# ICE40.net
KiCad netlist of a schematic drawn in Altium Designer
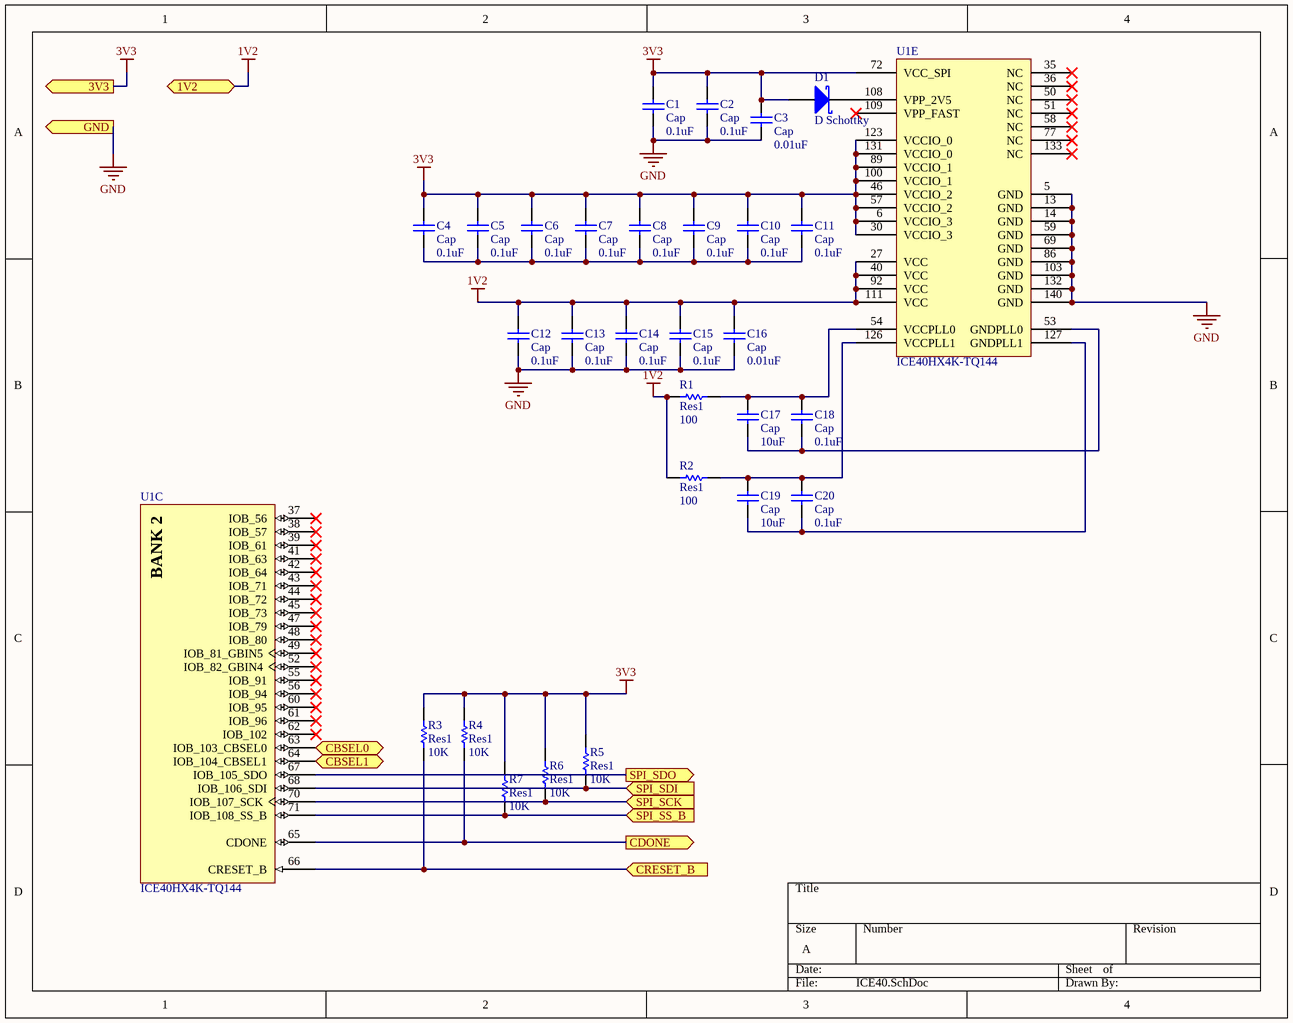
[diagram p0: ICE40.SchDoc]

(export (version "E")
  (design (tool "Eeschema 10.0.6"))
  (components
    (comp (ref "C1")
      (value "Cap")
      (footprint "RAD-0.3")
      (description "Capacitor")
      (fields (field (name "ALTIUM_VALUE") "0.1uF") (field (name "PUBLISHER") "Altium Limited"))
      (libsource (lib "Miscellaneous Devices") (part "Cap"))
    )
    (comp (ref "C2")
      (value "Cap")
      (footprint "RAD-0.3")
      (description "Capacitor")
      (fields (field (name "ALTIUM_VALUE") "0.1uF") (field (name "PUBLISHER") "Altium Limited"))
      (libsource (lib "Miscellaneous Devices") (part "Cap"))
    )
    (comp (ref "C3")
      (value "Cap")
      (footprint "RAD-0.3")
      (description "Capacitor")
      (fields (field (name "ALTIUM_VALUE") "0.01uF") (field (name "PUBLISHER") "Altium Limited"))
      (libsource (lib "Miscellaneous Devices") (part "Cap"))
    )
    (comp (ref "C4")
      (value "Cap")
      (footprint "RAD-0.3")
      (description "Capacitor")
      (fields (field (name "ALTIUM_VALUE") "0.1uF") (field (name "PUBLISHER") "Altium Limited"))
      (libsource (lib "Miscellaneous Devices") (part "Cap"))
    )
    (comp (ref "C5")
      (value "Cap")
      (footprint "RAD-0.3")
      (description "Capacitor")
      (fields (field (name "ALTIUM_VALUE") "0.1uF") (field (name "PUBLISHER") "Altium Limited"))
      (libsource (lib "Miscellaneous Devices") (part "Cap"))
    )
    (comp (ref "C6")
      (value "Cap")
      (footprint "RAD-0.3")
      (description "Capacitor")
      (fields (field (name "ALTIUM_VALUE") "0.1uF") (field (name "PUBLISHER") "Altium Limited"))
      (libsource (lib "Miscellaneous Devices") (part "Cap"))
    )
    (comp (ref "C7")
      (value "Cap")
      (footprint "RAD-0.3")
      (description "Capacitor")
      (fields (field (name "ALTIUM_VALUE") "0.1uF") (field (name "PUBLISHER") "Altium Limited"))
      (libsource (lib "Miscellaneous Devices") (part "Cap"))
    )
    (comp (ref "C8")
      (value "Cap")
      (footprint "RAD-0.3")
      (description "Capacitor")
      (fields (field (name "ALTIUM_VALUE") "0.1uF") (field (name "PUBLISHER") "Altium Limited"))
      (libsource (lib "Miscellaneous Devices") (part "Cap"))
    )
    (comp (ref "C9")
      (value "Cap")
      (footprint "RAD-0.3")
      (description "Capacitor")
      (fields (field (name "ALTIUM_VALUE") "0.1uF") (field (name "PUBLISHER") "Altium Limited"))
      (libsource (lib "Miscellaneous Devices") (part "Cap"))
    )
    (comp (ref "C10")
      (value "Cap")
      (footprint "RAD-0.3")
      (description "Capacitor")
      (fields (field (name "ALTIUM_VALUE") "0.1uF") (field (name "PUBLISHER") "Altium Limited"))
      (libsource (lib "Miscellaneous Devices") (part "Cap"))
    )
    (comp (ref "C11")
      (value "Cap")
      (footprint "RAD-0.3")
      (description "Capacitor")
      (fields (field (name "ALTIUM_VALUE") "0.1uF") (field (name "PUBLISHER") "Altium Limited"))
      (libsource (lib "Miscellaneous Devices") (part "Cap"))
    )
    (comp (ref "C12")
      (value "Cap")
      (footprint "RAD-0.3")
      (description "Capacitor")
      (fields (field (name "ALTIUM_VALUE") "0.1uF") (field (name "PUBLISHER") "Altium Limited"))
      (libsource (lib "Miscellaneous Devices") (part "Cap"))
    )
    (comp (ref "C13")
      (value "Cap")
      (footprint "RAD-0.3")
      (description "Capacitor")
      (fields (field (name "ALTIUM_VALUE") "0.1uF") (field (name "PUBLISHER") "Altium Limited"))
      (libsource (lib "Miscellaneous Devices") (part "Cap"))
    )
    (comp (ref "C14")
      (value "Cap")
      (footprint "RAD-0.3")
      (description "Capacitor")
      (fields (field (name "ALTIUM_VALUE") "0.1uF") (field (name "PUBLISHER") "Altium Limited"))
      (libsource (lib "Miscellaneous Devices") (part "Cap"))
    )
    (comp (ref "C15")
      (value "Cap")
      (footprint "RAD-0.3")
      (description "Capacitor")
      (fields (field (name "ALTIUM_VALUE") "0.1uF") (field (name "PUBLISHER") "Altium Limited"))
      (libsource (lib "Miscellaneous Devices") (part "Cap"))
    )
    (comp (ref "C16")
      (value "Cap")
      (footprint "RAD-0.3")
      (description "Capacitor")
      (fields (field (name "ALTIUM_VALUE") "0.01uF") (field (name "PUBLISHER") "Altium Limited"))
      (libsource (lib "Miscellaneous Devices") (part "Cap"))
    )
    (comp (ref "C17")
      (value "Cap")
      (footprint "RAD-0.3")
      (description "Capacitor")
      (fields (field (name "ALTIUM_VALUE") "10uF") (field (name "PUBLISHER") "Altium Limited"))
      (libsource (lib "Miscellaneous Devices") (part "Cap"))
    )
    (comp (ref "C18")
      (value "Cap")
      (footprint "RAD-0.3")
      (description "Capacitor")
      (fields (field (name "ALTIUM_VALUE") "0.1uF") (field (name "PUBLISHER") "Altium Limited"))
      (libsource (lib "Miscellaneous Devices") (part "Cap"))
    )
    (comp (ref "C19")
      (value "Cap")
      (footprint "RAD-0.3")
      (description "Capacitor")
      (fields (field (name "ALTIUM_VALUE") "10uF") (field (name "PUBLISHER") "Altium Limited"))
      (libsource (lib "Miscellaneous Devices") (part "Cap"))
    )
    (comp (ref "C20")
      (value "Cap")
      (footprint "RAD-0.3")
      (description "Capacitor")
      (fields (field (name "ALTIUM_VALUE") "0.1uF") (field (name "PUBLISHER") "Altium Limited"))
      (libsource (lib "Miscellaneous Devices") (part "Cap"))
    )
    (comp (ref "D1")
      (value "D Schottky")
      (footprint "SMB")
      (description "Schottky Diode")
      (fields (field (name "PUBLISHER") "Altium Limited"))
      (libsource (lib "Miscellaneous Devices") (part "D Schottky"))
    )
    (comp (ref "R1")
      (value "Res1")
      (footprint "AXIAL-0.3")
      (description "Resistor")
      (fields (field (name "ALTIUM_VALUE") "100") (field (name "PUBLISHER") "Altium Limited"))
      (libsource (lib "Miscellaneous Devices") (part "Res1"))
    )
    (comp (ref "R2")
      (value "Res1")
      (footprint "AXIAL-0.3")
      (description "Resistor")
      (fields (field (name "ALTIUM_VALUE") "100") (field (name "PUBLISHER") "Altium Limited"))
      (libsource (lib "Miscellaneous Devices") (part "Res1"))
    )
    (comp (ref "R3")
      (value "Res1")
      (footprint "AXIAL-0.3")
      (description "Resistor")
      (fields (field (name "ALTIUM_VALUE") "10K") (field (name "PUBLISHER") "Altium Limited"))
      (libsource (lib "Miscellaneous Devices") (part "Res1"))
    )
    (comp (ref "R4")
      (value "Res1")
      (footprint "AXIAL-0.3")
      (description "Resistor")
      (fields (field (name "ALTIUM_VALUE") "10K") (field (name "PUBLISHER") "Altium Limited"))
      (libsource (lib "Miscellaneous Devices") (part "Res1"))
    )
    (comp (ref "R5")
      (value "Res1")
      (footprint "AXIAL-0.3")
      (description "Resistor")
      (fields (field (name "ALTIUM_VALUE") "10K") (field (name "PUBLISHER") "Altium Limited"))
      (libsource (lib "Miscellaneous Devices") (part "Res1"))
    )
    (comp (ref "R6")
      (value "Res1")
      (footprint "AXIAL-0.3")
      (description "Resistor")
      (fields (field (name "ALTIUM_VALUE") "10K") (field (name "PUBLISHER") "Altium Limited"))
      (libsource (lib "Miscellaneous Devices") (part "Res1"))
    )
    (comp (ref "R7")
      (value "Res1")
      (footprint "AXIAL-0.3")
      (description "Resistor")
      (fields (field (name "ALTIUM_VALUE") "10K") (field (name "PUBLISHER") "Altium Limited"))
      (libsource (lib "Miscellaneous Devices") (part "Res1"))
    )
    (comp (ref "U1")
      (value "ICE40HX4K-TQ144")
      (footprint "LATC-TQFP-144_M")
      (fields (field (name "MANUFACTURER") "Lattice Semiconductor"))
      (libsource (lib "Lattice iCE40") (part "ICE40HX4K-TQ144"))
    )
  )
  (nets
    (net (code "1") (name "/CBSEL0") (class "Default")
      (node (ref "U1") (pin "63") (pinfunction "IOB_103_CBSEL0_63") (pintype "bidirectional"))
    )
    (net (code "2") (name "/CBSEL1") (class "Default")
      (node (ref "U1") (pin "64") (pinfunction "IOB_104_CBSEL1_64") (pintype "bidirectional"))
    )
    (net (code "3") (name "/CDONE") (class "Default")
      (node (ref "R4") (pin "1") (pinfunction "1_1") (pintype "passive"))
      (node (ref "U1") (pin "65") (pinfunction "CDONE_65") (pintype "bidirectional"))
    )
    (net (code "4") (name "/CRESET_B") (class "Default")
      (node (ref "R3") (pin "1") (pinfunction "1_1") (pintype "passive"))
      (node (ref "U1") (pin "66") (pinfunction "CRESET_B_66") (pintype "input"))
    )
    (net (code "5") (name "/SPI_SCK") (class "Default")
      (node (ref "R6") (pin "1") (pinfunction "1_1") (pintype "passive"))
      (node (ref "U1") (pin "70") (pinfunction "IOB_107_SCK_70") (pintype "bidirectional"))
    )
    (net (code "6") (name "/SPI_SDI") (class "Default")
      (node (ref "R5") (pin "1") (pinfunction "1_1") (pintype "passive"))
      (node (ref "U1") (pin "68") (pinfunction "IOB_106_SDI_68") (pintype "bidirectional"))
    )
    (net (code "7") (name "/SPI_SDO") (class "Default")
      (node (ref "U1") (pin "67") (pinfunction "IOB_105_SDO_67") (pintype "bidirectional"))
    )
    (net (code "8") (name "/SPI_SS_B") (class "Default")
      (node (ref "R7") (pin "1") (pinfunction "1_1") (pintype "passive"))
      (node (ref "U1") (pin "71") (pinfunction "IOB_108_SS_B_71") (pintype "bidirectional"))
    )
    (net (code "9") (name "1V2") (class "Default")
      (node (ref "C12") (pin "1") (pinfunction "1_1") (pintype "passive"))
      (node (ref "C13") (pin "1") (pinfunction "1_1") (pintype "passive"))
      (node (ref "C14") (pin "1") (pinfunction "1_1") (pintype "passive"))
      (node (ref "C15") (pin "1") (pinfunction "1_1") (pintype "passive"))
      (node (ref "C16") (pin "1") (pinfunction "1_1") (pintype "passive"))
      (node (ref "R1") (pin "1") (pinfunction "1_1") (pintype "passive"))
      (node (ref "R2") (pin "1") (pinfunction "1_1") (pintype "passive"))
      (node (ref "U1") (pin "111") (pinfunction "VCC_111") (pintype "power_in"))
      (node (ref "U1") (pin "27") (pinfunction "VCC_27") (pintype "power_in"))
      (node (ref "U1") (pin "40") (pinfunction "VCC_40") (pintype "power_in"))
      (node (ref "U1") (pin "92") (pinfunction "VCC_92") (pintype "power_in"))
    )
    (net (code "10") (name "3V3") (class "Default")
      (node (ref "C1") (pin "1") (pinfunction "1_1") (pintype "passive"))
      (node (ref "C10") (pin "1") (pinfunction "1_1") (pintype "passive"))
      (node (ref "C11") (pin "1") (pinfunction "1_1") (pintype "passive"))
      (node (ref "C2") (pin "1") (pinfunction "1_1") (pintype "passive"))
      (node (ref "C3") (pin "1") (pinfunction "1_1") (pintype "passive"))
      (node (ref "C4") (pin "1") (pinfunction "1_1") (pintype "passive"))
      (node (ref "C5") (pin "1") (pinfunction "1_1") (pintype "passive"))
      (node (ref "C6") (pin "1") (pinfunction "1_1") (pintype "passive"))
      (node (ref "C7") (pin "1") (pinfunction "1_1") (pintype "passive"))
      (node (ref "C8") (pin "1") (pinfunction "1_1") (pintype "passive"))
      (node (ref "C9") (pin "1") (pinfunction "1_1") (pintype "passive"))
      (node (ref "D1") (pin "1") (pinfunction "A_1") (pintype "passive"))
      (node (ref "R3") (pin "2") (pinfunction "2_2") (pintype "passive"))
      (node (ref "R4") (pin "2") (pinfunction "2_2") (pintype "passive"))
      (node (ref "R5") (pin "2") (pinfunction "2_2") (pintype "passive"))
      (node (ref "R6") (pin "2") (pinfunction "2_2") (pintype "passive"))
      (node (ref "R7") (pin "2") (pinfunction "2_2") (pintype "passive"))
      (node (ref "U1") (pin "100") (pinfunction "VCCIO_1_100") (pintype "power_in"))
      (node (ref "U1") (pin "123") (pinfunction "VCCIO_0_123") (pintype "power_in"))
      (node (ref "U1") (pin "131") (pinfunction "VCCIO_0_131") (pintype "power_in"))
      (node (ref "U1") (pin "30") (pinfunction "VCCIO_3_30") (pintype "power_in"))
      (node (ref "U1") (pin "46") (pinfunction "VCCIO_2_46") (pintype "power_in"))
      (node (ref "U1") (pin "57") (pinfunction "VCCIO_2_57") (pintype "power_in"))
      (node (ref "U1") (pin "6") (pinfunction "VCCIO_3_6") (pintype "power_in"))
      (node (ref "U1") (pin "72") (pinfunction "VCC_SPI_72") (pintype "power_in"))
      (node (ref "U1") (pin "89") (pinfunction "VCCIO_1_89") (pintype "power_in"))
    )
    (net (code "11") (name "GND") (class "Default")
      (node (ref "C1") (pin "2") (pinfunction "2_2") (pintype "passive"))
      (node (ref "C12") (pin "2") (pinfunction "2_2") (pintype "passive"))
      (node (ref "C13") (pin "2") (pinfunction "2_2") (pintype "passive"))
      (node (ref "C14") (pin "2") (pinfunction "2_2") (pintype "passive"))
      (node (ref "C15") (pin "2") (pinfunction "2_2") (pintype "passive"))
      (node (ref "C16") (pin "2") (pinfunction "2_2") (pintype "passive"))
      (node (ref "C2") (pin "2") (pinfunction "2_2") (pintype "passive"))
      (node (ref "C3") (pin "2") (pinfunction "2_2") (pintype "passive"))
      (node (ref "U1") (pin "103") (pinfunction "GND_103") (pintype "power_in"))
      (node (ref "U1") (pin "13") (pinfunction "GND_13") (pintype "power_in"))
      (node (ref "U1") (pin "132") (pinfunction "GND_132") (pintype "power_in"))
      (node (ref "U1") (pin "14") (pinfunction "GND_14") (pintype "power_in"))
      (node (ref "U1") (pin "140") (pinfunction "GND_140") (pintype "power_in"))
      (node (ref "U1") (pin "5") (pinfunction "GND_5") (pintype "power_in"))
      (node (ref "U1") (pin "59") (pinfunction "GND_59") (pintype "power_in"))
      (node (ref "U1") (pin "69") (pinfunction "GND_69") (pintype "power_in"))
      (node (ref "U1") (pin "86") (pinfunction "GND_86") (pintype "power_in"))
    )
    (net (code "12") (name "Net-(C10-Pad2)") (class "Default")
      (node (ref "C10") (pin "2") (pinfunction "2_2") (pintype "passive"))
      (node (ref "C11") (pin "2") (pinfunction "2_2") (pintype "passive"))
      (node (ref "C4") (pin "2") (pinfunction "2_2") (pintype "passive"))
      (node (ref "C5") (pin "2") (pinfunction "2_2") (pintype "passive"))
      (node (ref "C6") (pin "2") (pinfunction "2_2") (pintype "passive"))
      (node (ref "C7") (pin "2") (pinfunction "2_2") (pintype "passive"))
      (node (ref "C8") (pin "2") (pinfunction "2_2") (pintype "passive"))
      (node (ref "C9") (pin "2") (pinfunction "2_2") (pintype "passive"))
    )
    (net (code "13") (name "Net-(D1-K)") (class "Default")
      (node (ref "D1") (pin "2") (pinfunction "K_2") (pintype "passive"))
      (node (ref "U1") (pin "108") (pinfunction "VPP_2V5_108") (pintype "power_in"))
    )
    (net (code "14") (name "Net-(U1E-GNDPLL0)") (class "Default")
      (node (ref "C17") (pin "2") (pinfunction "2_2") (pintype "passive"))
      (node (ref "C18") (pin "2") (pinfunction "2_2") (pintype "passive"))
      (node (ref "U1") (pin "53") (pinfunction "GNDPLL0_53") (pintype "power_in"))
    )
    (net (code "15") (name "Net-(U1E-GNDPLL1)") (class "Default")
      (node (ref "C19") (pin "2") (pinfunction "2_2") (pintype "passive"))
      (node (ref "C20") (pin "2") (pinfunction "2_2") (pintype "passive"))
      (node (ref "U1") (pin "127") (pinfunction "GNDPLL1_127") (pintype "power_in"))
    )
    (net (code "16") (name "Net-(U1E-VCCPLL0)") (class "Default")
      (node (ref "C17") (pin "1") (pinfunction "1_1") (pintype "passive"))
      (node (ref "C18") (pin "1") (pinfunction "1_1") (pintype "passive"))
      (node (ref "R1") (pin "2") (pinfunction "2_2") (pintype "passive"))
      (node (ref "U1") (pin "54") (pinfunction "VCCPLL0_54") (pintype "power_in"))
    )
    (net (code "17") (name "Net-(U1E-VCCPLL1)") (class "Default")
      (node (ref "C19") (pin "1") (pinfunction "1_1") (pintype "passive"))
      (node (ref "C20") (pin "1") (pinfunction "1_1") (pintype "passive"))
      (node (ref "R2") (pin "2") (pinfunction "2_2") (pintype "passive"))
      (node (ref "U1") (pin "126") (pinfunction "VCCPLL1_126") (pintype "power_in"))
    )
    (net (code "18") (name "unconnected-(U1C-IOB_56-Pad37)") (class "Default")
      (node (ref "U1") (pin "37") (pinfunction "IOB_56_37") (pintype "bidirectional+no_connect"))
    )
    (net (code "19") (name "unconnected-(U1C-IOB_57-Pad38)") (class "Default")
      (node (ref "U1") (pin "38") (pinfunction "IOB_57_38") (pintype "bidirectional+no_connect"))
    )
    (net (code "20") (name "unconnected-(U1C-IOB_61-Pad39)") (class "Default")
      (node (ref "U1") (pin "39") (pinfunction "IOB_61_39") (pintype "bidirectional+no_connect"))
    )
    (net (code "21") (name "unconnected-(U1C-IOB_63-Pad41)") (class "Default")
      (node (ref "U1") (pin "41") (pinfunction "IOB_63_41") (pintype "bidirectional+no_connect"))
    )
    (net (code "22") (name "unconnected-(U1C-IOB_64-Pad42)") (class "Default")
      (node (ref "U1") (pin "42") (pinfunction "IOB_64_42") (pintype "bidirectional+no_connect"))
    )
    (net (code "23") (name "unconnected-(U1C-IOB_71-Pad43)") (class "Default")
      (node (ref "U1") (pin "43") (pinfunction "IOB_71_43") (pintype "bidirectional+no_connect"))
    )
    (net (code "24") (name "unconnected-(U1C-IOB_72-Pad44)") (class "Default")
      (node (ref "U1") (pin "44") (pinfunction "IOB_72_44") (pintype "bidirectional+no_connect"))
    )
    (net (code "25") (name "unconnected-(U1C-IOB_73-Pad45)") (class "Default")
      (node (ref "U1") (pin "45") (pinfunction "IOB_73_45") (pintype "bidirectional+no_connect"))
    )
    (net (code "26") (name "unconnected-(U1C-IOB_79-Pad47)") (class "Default")
      (node (ref "U1") (pin "47") (pinfunction "IOB_79_47") (pintype "bidirectional+no_connect"))
    )
    (net (code "27") (name "unconnected-(U1C-IOB_80-Pad48)") (class "Default")
      (node (ref "U1") (pin "48") (pinfunction "IOB_80_48") (pintype "bidirectional+no_connect"))
    )
    (net (code "28") (name "unconnected-(U1C-IOB_81_GBIN5-Pad49)") (class "Default")
      (node (ref "U1") (pin "49") (pinfunction "IOB_81_GBIN5_49") (pintype "bidirectional+no_connect"))
    )
    (net (code "29") (name "unconnected-(U1C-IOB_82_GBIN4-Pad52)") (class "Default")
      (node (ref "U1") (pin "52") (pinfunction "IOB_82_GBIN4_52") (pintype "bidirectional+no_connect"))
    )
    (net (code "30") (name "unconnected-(U1C-IOB_91-Pad55)") (class "Default")
      (node (ref "U1") (pin "55") (pinfunction "IOB_91_55") (pintype "bidirectional+no_connect"))
    )
    (net (code "31") (name "unconnected-(U1C-IOB_94-Pad56)") (class "Default")
      (node (ref "U1") (pin "56") (pinfunction "IOB_94_56") (pintype "bidirectional+no_connect"))
    )
    (net (code "32") (name "unconnected-(U1C-IOB_95-Pad60)") (class "Default")
      (node (ref "U1") (pin "60") (pinfunction "IOB_95_60") (pintype "bidirectional+no_connect"))
    )
    (net (code "33") (name "unconnected-(U1C-IOB_96-Pad61)") (class "Default")
      (node (ref "U1") (pin "61") (pinfunction "IOB_96_61") (pintype "bidirectional+no_connect"))
    )
    (net (code "34") (name "unconnected-(U1C-IOB_102-Pad62)") (class "Default")
      (node (ref "U1") (pin "62") (pinfunction "IOB_102_62") (pintype "bidirectional+no_connect"))
    )
    (net (code "35") (name "unconnected-(U1E-NC-Pad35)") (class "Default")
      (node (ref "U1") (pin "35") (pinfunction "NC_35") (pintype "passive+no_connect"))
    )
    (net (code "36") (name "unconnected-(U1E-NC-Pad36)") (class "Default")
      (node (ref "U1") (pin "36") (pinfunction "NC_36") (pintype "passive+no_connect"))
    )
    (net (code "37") (name "unconnected-(U1E-NC-Pad50)") (class "Default")
      (node (ref "U1") (pin "50") (pinfunction "NC_50") (pintype "passive+no_connect"))
    )
    (net (code "38") (name "unconnected-(U1E-NC-Pad51)") (class "Default")
      (node (ref "U1") (pin "51") (pinfunction "NC_51") (pintype "passive+no_connect"))
    )
    (net (code "39") (name "unconnected-(U1E-NC-Pad58)") (class "Default")
      (node (ref "U1") (pin "58") (pinfunction "NC_58") (pintype "passive+no_connect"))
    )
    (net (code "40") (name "unconnected-(U1E-NC-Pad77)") (class "Default")
      (node (ref "U1") (pin "77") (pinfunction "NC_77") (pintype "passive+no_connect"))
    )
    (net (code "41") (name "unconnected-(U1E-NC-Pad133)") (class "Default")
      (node (ref "U1") (pin "133") (pinfunction "NC_133") (pintype "passive+no_connect"))
    )
    (net (code "42") (name "unconnected-(U1E-VPP_FAST-Pad109)") (class "Default")
      (node (ref "U1") (pin "109") (pinfunction "VPP_FAST_109") (pintype "power_in+no_connect"))
    )
  )
)
